# CODEC_and_Headphone_Jack.net
KiCad netlist of a schematic drawn in Altium Designer
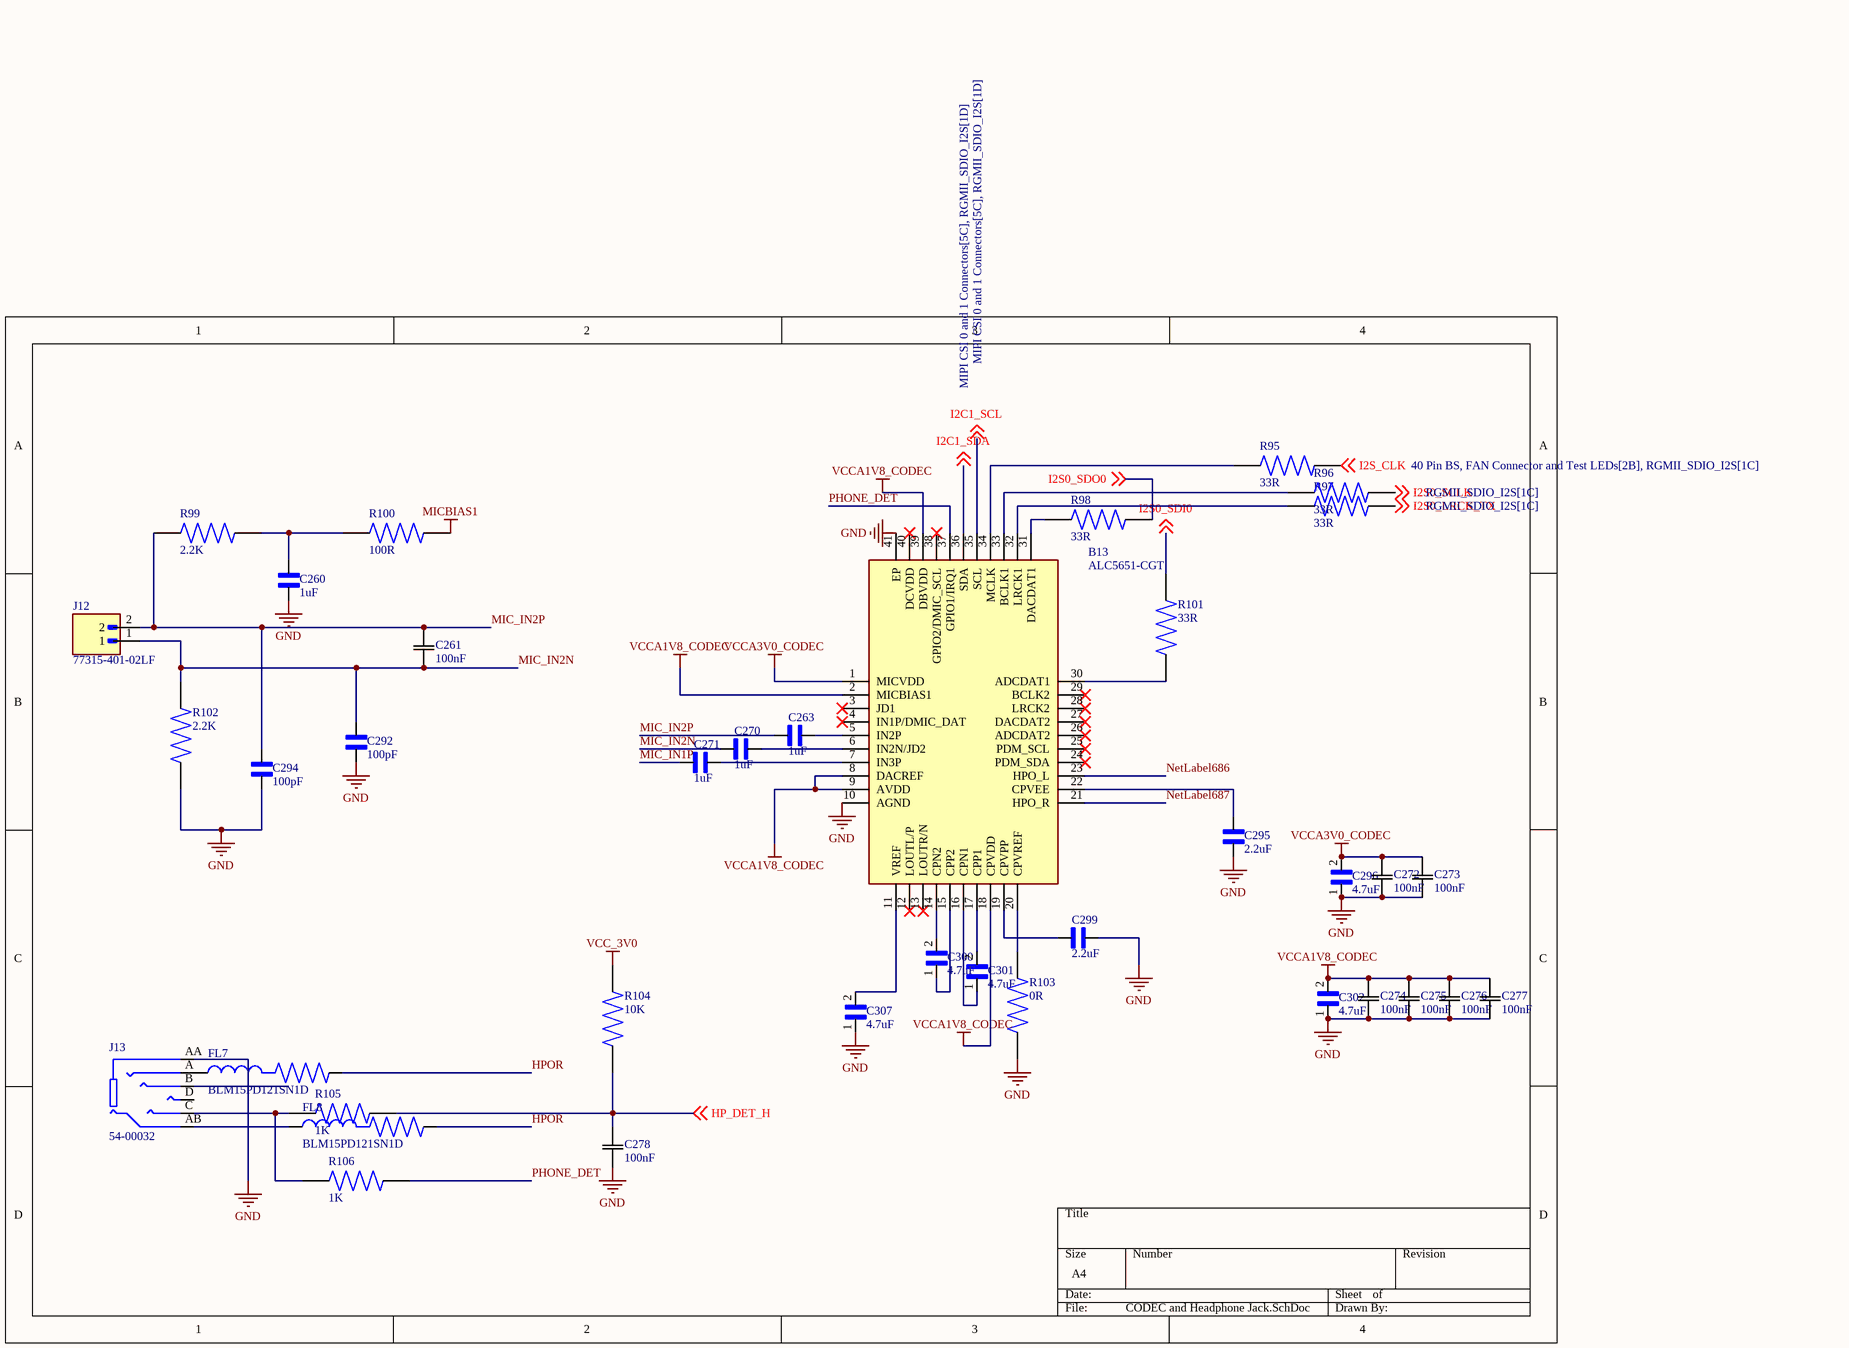
[diagram p0: CODEC and Headphone Jack.SchDoc]

(export (version "E")
  (design (tool "Eeschema 10.0.6"))
  (components
    (comp (ref "B13")
      (value "ALC5651-CGT")
      (footprint "QFN40P500X500X90-41N-D")
      (libsource (lib "ALC5651-CGT") (part "ALC5651-CGT"))
    )
    (comp (ref "C260")
      (value "1uF")
      (footprint "CAPC1005X56N")
      (description "1 ÂµF Â±10% 10V Ceramic Capacitor X5R 0402 (1005 Metric)")
      (fields (field (name "MF") "AVX") (field (name "MP") "0402ZD105KAT4A"))
      (libsource (lib "0402ZD105KAT4A") (part "0402ZD105KAT4A"))
    )
    (comp (ref "C261")
      (value "100nF")
      (footprint "CAP_1005_TDK")
      (description "Description")
      (fields
        (field (name "MANUFACTURER_PART_NUMBER") "C1005X7R1H104M050BB")
        (field (name "COPYRIGHT") "Copyright (C) 2025 Ultra Librarian. All rights reserved.")
      )
      (libsource (lib "C1005X7R1H104M050BB") (part "C1005X7R1H104M050BB"))
    )
    (comp (ref "C263")
      (value "1uF")
      (footprint "CAPC1005X56N")
      (description "1 ÂµF Â±10% 10V Ceramic Capacitor X5R 0402 (1005 Metric)")
      (fields (field (name "MF") "AVX") (field (name "MP") "0402ZD105KAT4A"))
      (libsource (lib "") (part "0402ZD105KAT4A_1"))
    )
    (comp (ref "C270")
      (value "1uF")
      (footprint "CAPC1005X56N")
      (description "1 ÂµF Â±10% 10V Ceramic Capacitor X5R 0402 (1005 Metric)")
      (fields (field (name "MF") "AVX") (field (name "MP") "0402ZD105KAT4A"))
      (libsource (lib "") (part "0402ZD105KAT4A_1"))
    )
    (comp (ref "C271")
      (value "1uF")
      (footprint "CAPC1005X56N")
      (description "1 ÂµF Â±10% 10V Ceramic Capacitor X5R 0402 (1005 Metric)")
      (fields (field (name "MF") "AVX") (field (name "MP") "0402ZD105KAT4A"))
      (libsource (lib "") (part "0402ZD105KAT4A_1"))
    )
    (comp (ref "C272")
      (value "100nF")
      (footprint "CAP_1005_TDK")
      (description "Description")
      (fields
        (field (name "MANUFACTURER_PART_NUMBER") "C1005X7R1H104M050BB")
        (field (name "COPYRIGHT") "Copyright (C) 2025 Ultra Librarian. All rights reserved.")
      )
      (libsource (lib "C1005X7R1H104M050BB") (part "C1005X7R1H104M050BB"))
    )
    (comp (ref "C273")
      (value "100nF")
      (footprint "CAP_1005_TDK")
      (description "Description")
      (fields
        (field (name "MANUFACTURER_PART_NUMBER") "C1005X7R1H104M050BB")
        (field (name "COPYRIGHT") "Copyright (C) 2025 Ultra Librarian. All rights reserved.")
      )
      (libsource (lib "C1005X7R1H104M050BB") (part "C1005X7R1H104M050BB"))
    )
    (comp (ref "C274")
      (value "100nF")
      (footprint "CAP_1005_TDK")
      (description "Description")
      (fields
        (field (name "MANUFACTURER_PART_NUMBER") "C1005X7R1H104M050BB")
        (field (name "COPYRIGHT") "Copyright (C) 2025 Ultra Librarian. All rights reserved.")
      )
      (libsource (lib "C1005X7R1H104M050BB") (part "C1005X7R1H104M050BB"))
    )
    (comp (ref "C275")
      (value "100nF")
      (footprint "CAP_1005_TDK")
      (description "Description")
      (fields
        (field (name "MANUFACTURER_PART_NUMBER") "C1005X7R1H104M050BB")
        (field (name "COPYRIGHT") "Copyright (C) 2025 Ultra Librarian. All rights reserved.")
      )
      (libsource (lib "C1005X7R1H104M050BB") (part "C1005X7R1H104M050BB"))
    )
    (comp (ref "C276")
      (value "100nF")
      (footprint "CAP_1005_TDK")
      (description "Description")
      (fields
        (field (name "MANUFACTURER_PART_NUMBER") "C1005X7R1H104M050BB")
        (field (name "COPYRIGHT") "Copyright (C) 2025 Ultra Librarian. All rights reserved.")
      )
      (libsource (lib "C1005X7R1H104M050BB") (part "C1005X7R1H104M050BB"))
    )
    (comp (ref "C277")
      (value "100nF")
      (footprint "CAP_1005_TDK")
      (description "Description")
      (fields
        (field (name "MANUFACTURER_PART_NUMBER") "C1005X7R1H104M050BB")
        (field (name "COPYRIGHT") "Copyright (C) 2025 Ultra Librarian. All rights reserved.")
      )
      (libsource (lib "C1005X7R1H104M050BB") (part "C1005X7R1H104M050BB"))
    )
    (comp (ref "C278")
      (value "100nF")
      (footprint "CAP_1005_TDK")
      (description "Description")
      (fields
        (field (name "MANUFACTURER_PART_NUMBER") "C1005X7R1H104M050BB")
        (field (name "COPYRIGHT") "Copyright (C) 2025 Ultra Librarian. All rights reserved.")
      )
      (libsource (lib "C1005X7R1H104M050BB") (part "C1005X7R1H104M050BB"))
    )
    (comp (ref "C292")
      (value "100pF")
      (footprint "CAPC2012X140N")
      (description "Capacitor, Ceramic, Cap, 22.0pF, Tol 5%, SMT, 50V, C0G ¦ KEMET C0805C220J5GACTU")
      (fields (field (name "MF") "KEMET") (field (name "MP") "C0805C220J5GACTU"))
      (libsource (lib "C0805C220J5GACTU") (part "C0805C220J5GACTU"))
    )
    (comp (ref "C294")
      (value "100pF")
      (footprint "CAPC2012X140N")
      (description "Capacitor, Ceramic, Cap, 22.0pF, Tol 5%, SMT, 50V, C0G ¦ KEMET C0805C220J5GACTU")
      (fields (field (name "MF") "KEMET") (field (name "MP") "C0805C220J5GACTU"))
      (libsource (lib "C0805C220J5GACTU") (part "C0805C220J5GACTU"))
    )
    (comp (ref "C295")
      (value "2.2uF")
      (footprint "CAPC3225X140N")
      (description "Capacitor;Ceramic;Cap;1.00uF;Tol+10%;SMT;Vol-Rtg 50V;High Cap.;X7R;TR ¦ KEMET C1210C105K5RACTU")
      (fields (field (name "MF") "KEMET") (field (name "MP") "C1210C105K5RACTU"))
      (libsource (lib "C1210C105K5RACTU") (part "C1210C105K5RACTU"))
    )
    (comp (ref "C296")
      (value "4.7uF")
      (footprint "CAPC6050X350N")
      (description "CAP CER 4.7UF 100V X7R SMD")
      (fields (field (name "MF") "TDK") (field (name "MP") "CKG57KX7R2A475M335JJ"))
      (libsource (lib "CKG57KX7R2A475M335JJ") (part "CKG57KX7R2A475M335JJ"))
    )
    (comp (ref "C299")
      (value "2.2uF")
      (footprint "CAPC3225X140N")
      (description "Capacitor;Ceramic;Cap;1.00uF;Tol+10%;SMT;Vol-Rtg 50V;High Cap.;X7R;TR ¦ KEMET C1210C105K5RACTU")
      (fields (field (name "MF") "KEMET") (field (name "MP") "C1210C105K5RACTU"))
      (libsource (lib "") (part "C1210C105K5RACTU_1"))
    )
    (comp (ref "C300")
      (value "4.7uF")
      (footprint "CAPC6050X350N")
      (description "CAP CER 4.7UF 100V X7R SMD")
      (fields (field (name "MF") "TDK") (field (name "MP") "CKG57KX7R2A475M335JJ"))
      (libsource (lib "CKG57KX7R2A475M335JJ") (part "CKG57KX7R2A475M335JJ"))
    )
    (comp (ref "C301")
      (value "4.7uF")
      (footprint "CAPC6050X350N")
      (description "CAP CER 4.7UF 100V X7R SMD")
      (fields (field (name "MF") "TDK") (field (name "MP") "CKG57KX7R2A475M335JJ"))
      (libsource (lib "CKG57KX7R2A475M335JJ") (part "CKG57KX7R2A475M335JJ"))
    )
    (comp (ref "C302")
      (value "4.7uF")
      (footprint "CAPC6050X350N")
      (description "CAP CER 4.7UF 100V X7R SMD")
      (fields (field (name "MF") "TDK") (field (name "MP") "CKG57KX7R2A475M335JJ"))
      (libsource (lib "CKG57KX7R2A475M335JJ") (part "CKG57KX7R2A475M335JJ"))
    )
    (comp (ref "C307")
      (value "4.7uF")
      (footprint "CAPC6050X350N")
      (description "CAP CER 4.7UF 100V X7R SMD")
      (fields (field (name "MF") "TDK") (field (name "MP") "CKG57KX7R2A475M335JJ"))
      (libsource (lib "CKG57KX7R2A475M335JJ") (part "CKG57KX7R2A475M335JJ"))
    )
    (comp (ref "FL7")
      (value "BLM15PD121SN1D")
      (footprint "BEADC1005X55N")
      (description "120 Ohms @ 100 MHz 1 Power Line Ferrite Bead 0402 (1005 Metric) 1.3A 90mOhm")
      (fields (field (name "MF") "Murata"))
      (libsource (lib "BLM15PD121SN1D") (part "BLM15PD121SN1D"))
    )
    (comp (ref "FL8")
      (value "BLM15PD121SN1D")
      (footprint "BEADC1005X55N")
      (description "120 Ohms @ 100 MHz 1 Power Line Ferrite Bead 0402 (1005 Metric) 1.3A 90mOhm")
      (fields (field (name "MF") "Murata"))
      (libsource (lib "BLM15PD121SN1D") (part "BLM15PD121SN1D"))
    )
    (comp (ref "J12")
      (value "77315-401-02LF")
      (footprint "AMPHENOL_77315-401-02LF")
      (libsource (lib "77315-401-02LF") (part "77315-401-02LF"))
    )
    (comp (ref "J13")
      (value "54-00032")
      (footprint "TENSILITY_54-00032")
      (description "Connector, 6C audio jack, 3.5xL18.6 mm, PCB mount, 90 degrees, Au plated")
      (fields (field (name "MF") "Tensility International"))
      (libsource (lib "54-00032") (part "54-00032"))
    )
    (comp (ref "R95")
      (value "33R")
      (footprint "RES_ERA6AHD330V")
      (fields (field (name "MP") "ERA6AHD330V"))
      (libsource (lib "ERA6AHD330V") (part "ERA6AHD330V"))
    )
    (comp (ref "R96")
      (value "33R")
      (footprint "RES_ERA6AHD330V")
      (fields (field (name "MP") "ERA6AHD330V"))
      (libsource (lib "ERA6AHD330V") (part "ERA6AHD330V"))
    )
    (comp (ref "R97")
      (value "33R")
      (footprint "RES_ERA6AHD330V")
      (fields (field (name "MP") "ERA6AHD330V"))
      (libsource (lib "ERA6AHD330V") (part "ERA6AHD330V"))
    )
    (comp (ref "R98")
      (value "33R")
      (footprint "RES_ERA6AHD330V")
      (fields (field (name "MP") "ERA6AHD330V"))
      (libsource (lib "ERA6AHD330V") (part "ERA6AHD330V"))
    )
    (comp (ref "R99")
      (value "2.2K")
      (footprint "RESC1608X50N")
      (description "RR Series 0603 0.0625 W 2.2 kOhm Â± 0.5% Â±25 ppm/Â°C SMT Metal Film Chip Resistor")
      (fields (field (name "MF") "Susumu") (field (name "MP") "RR0816P-222-D"))
      (libsource (lib "RR0816P-222-D") (part "RR0816P-222-D"))
    )
    (comp (ref "R100")
      (value "100R")
      (footprint "RES_ERJU14F1000U")
      (fields (field (name "MP") "ERJU14F1000U"))
      (libsource (lib "ERJU14F1000U") (part "ERJU14F1000U"))
    )
    (comp (ref "R101")
      (value "33R")
      (footprint "RES_ERA6AHD330V")
      (fields (field (name "MP") "ERA6AHD330V"))
      (libsource (lib "ERA6AHD330V") (part "ERA6AHD330V"))
    )
    (comp (ref "R102")
      (value "2.2K")
      (footprint "RESC1608X50N")
      (description "RR Series 0603 0.0625 W 2.2 kOhm Â± 0.5% Â±25 ppm/Â°C SMT Metal Film Chip Resistor")
      (fields (field (name "MF") "Susumu") (field (name "MP") "RR0816P-222-D"))
      (libsource (lib "RR0816P-222-D") (part "RR0816P-222-D"))
    )
    (comp (ref "R103")
      (value "0R")
      (footprint "RES_ERJH6G0R00V")
      (fields (field (name "MP") "ERJH6G0R00V"))
      (libsource (lib "ERJH6G0R00V") (part "ERJH6G0R00V"))
    )
    (comp (ref "R104")
      (value "10K")
      (footprint "RES_ERA3ARB103V")
      (fields (field (name "MP") "ERA3ARB103V"))
      (libsource (lib "ERA3ARB103V") (part "ERA3ARB103V"))
    )
    (comp (ref "R105")
      (value "1K")
      (footprint "RESC1608X55N")
      (description "1 kOhms Â±1% 0.1W, 1/10W Chip Resistor 0603 (1608 Metric) - Thick Film")
      (fields (field (name "MF") "Vishay") (field (name "MP") "CRCW06031K00FKECC"))
      (libsource (lib "CRCW06031K00FKECC") (part "CRCW06031K00FKECC"))
    )
    (comp (ref "R106")
      (value "1K")
      (footprint "RESC1608X55N")
      (description "1 kOhms Â±1% 0.1W, 1/10W Chip Resistor 0603 (1608 Metric) - Thick Film")
      (fields (field (name "MF") "Vishay") (field (name "MP") "CRCW06031K00FKECC"))
      (libsource (lib "CRCW06031K00FKECC") (part "CRCW06031K00FKECC"))
    )
  )
  (nets
    (net (code "1") (name "/HPOR") (class "Default")
      (node (ref "FL7") (pin "2") (pinfunction "2_2") (pintype "passive"))
      (node (ref "FL8") (pin "2") (pinfunction "2_2") (pintype "passive"))
    )
    (net (code "2") (name "/MIC_IN1P") (class "Default")
      (node (ref "C271") (pin "2") (pinfunction "2_2") (pintype "passive"))
    )
    (net (code "3") (name "/MIC_IN2N") (class "Default")
      (node (ref "C261") (pin "1") (pinfunction "1_1") (pintype "passive"))
      (node (ref "C270") (pin "2") (pinfunction "2_2") (pintype "passive"))
      (node (ref "C292") (pin "1") (pinfunction "1_1") (pintype "passive"))
      (node (ref "J12") (pin "1") (pinfunction "1_1") (pintype "passive"))
      (node (ref "R102") (pin "2") (pinfunction "2_2") (pintype "passive"))
    )
    (net (code "4") (name "/MIC_IN2P") (class "Default")
      (node (ref "C261") (pin "2") (pinfunction "2_2") (pintype "passive"))
      (node (ref "C263") (pin "2") (pinfunction "2_2") (pintype "passive"))
      (node (ref "C294") (pin "1") (pinfunction "1_1") (pintype "passive"))
      (node (ref "J12") (pin "2") (pinfunction "2_2") (pintype "passive"))
      (node (ref "R99") (pin "1") (pinfunction "1_1") (pintype "passive"))
    )
    (net (code "5") (name "/NetLabel686") (class "Default")
      (node (ref "B13") (pin "23") (pinfunction "HPO_L_23") (pintype "passive"))
    )
    (net (code "6") (name "/NetLabel687") (class "Default")
      (node (ref "B13") (pin "21") (pinfunction "HPO_R_21") (pintype "passive"))
    )
    (net (code "7") (name "/PHONE_DET") (class "Default")
      (node (ref "B13") (pin "37") (pinfunction "GPIO1/IRQ1_37") (pintype "passive"))
      (node (ref "R106") (pin "2") (pinfunction "2_2") (pintype "passive"))
    )
    (net (code "8") (name "GND") (class "Default")
      (node (ref "B13") (pin "10") (pinfunction "AGND_10") (pintype "passive"))
      (node (ref "B13") (pin "41") (pinfunction "EP_41") (pintype "passive"))
      (node (ref "C260") (pin "1") (pinfunction "1_1") (pintype "passive"))
      (node (ref "C272") (pin "1") (pinfunction "1_1") (pintype "passive"))
      (node (ref "C273") (pin "1") (pinfunction "1_1") (pintype "passive"))
      (node (ref "C274") (pin "1") (pinfunction "1_1") (pintype "passive"))
      (node (ref "C275") (pin "1") (pinfunction "1_1") (pintype "passive"))
      (node (ref "C276") (pin "1") (pinfunction "1_1") (pintype "passive"))
      (node (ref "C277") (pin "1") (pinfunction "1_1") (pintype "passive"))
      (node (ref "C278") (pin "1") (pinfunction "1_1") (pintype "passive"))
      (node (ref "C292") (pin "2") (pinfunction "2_2") (pintype "passive"))
      (node (ref "C294") (pin "2") (pinfunction "2_2") (pintype "passive"))
      (node (ref "C295") (pin "1") (pinfunction "1_1") (pintype "passive"))
      (node (ref "C296") (pin "1") (pinfunction "1_1") (pintype "passive"))
      (node (ref "C299") (pin "1") (pinfunction "1_1") (pintype "passive"))
      (node (ref "C302") (pin "1") (pinfunction "1_1") (pintype "passive"))
      (node (ref "C307") (pin "1") (pinfunction "1_1") (pintype "passive"))
      (node (ref "J13") (pin "AA") (pinfunction "AA_AA") (pintype "passive"))
      (node (ref "R102") (pin "1") (pinfunction "1_1") (pintype "passive"))
      (node (ref "R103") (pin "1") (pinfunction "1_1") (pintype "passive"))
    )
    (net (code "9") (name "HP_DET_H") (class "Default")
      (node (ref "C278") (pin "2") (pinfunction "2_2") (pintype "passive"))
      (node (ref "R104") (pin "1") (pinfunction "1_1") (pintype "passive"))
      (node (ref "R105") (pin "2") (pinfunction "2_2") (pintype "passive"))
    )
    (net (code "10") (name "I2C1_SCL") (class "Default")
      (node (ref "B13") (pin "35") (pinfunction "SCL_35") (pintype "passive"))
    )
    (net (code "11") (name "I2C1_SDA") (class "Default")
      (node (ref "B13") (pin "36") (pinfunction "SDA_36") (pintype "passive"))
    )
    (net (code "12") (name "I2S0_LRCK_TX") (class "Default")
      (node (ref "R97") (pin "1") (pinfunction "1_1") (pintype "passive"))
    )
    (net (code "13") (name "I2S0_SCLK") (class "Default")
      (node (ref "R96") (pin "1") (pinfunction "1_1") (pintype "passive"))
    )
    (net (code "14") (name "I2S0_SDI0") (class "Default")
      (node (ref "R101") (pin "2") (pinfunction "2_2") (pintype "passive"))
    )
    (net (code "15") (name "I2S0_SDO0") (class "Default")
      (node (ref "R98") (pin "2") (pinfunction "2_2") (pintype "passive"))
    )
    (net (code "16") (name "I2S_CLK") (class "Default")
      (node (ref "R95") (pin "1") (pinfunction "1_1") (pintype "passive"))
    )
    (net (code "17") (name "MICBIAS1") (class "Default")
      (node (ref "R100") (pin "2") (pinfunction "2_2") (pintype "passive"))
    )
    (net (code "18") (name "Net-(B13-ADCDAT1)") (class "Default")
      (node (ref "B13") (pin "30") (pinfunction "ADCDAT1_30") (pintype "passive"))
      (node (ref "R101") (pin "1") (pinfunction "1_1") (pintype "passive"))
    )
    (net (code "19") (name "Net-(B13-BCLK1)") (class "Default")
      (node (ref "B13") (pin "33") (pinfunction "BCLK1_33") (pintype "passive"))
      (node (ref "R96") (pin "2") (pinfunction "2_2") (pintype "passive"))
    )
    (net (code "20") (name "Net-(B13-CPN1)") (class "Default")
      (node (ref "B13") (pin "16") (pinfunction "CPN1_16") (pintype "passive"))
      (node (ref "C301") (pin "1") (pinfunction "1_1") (pintype "passive"))
    )
    (net (code "21") (name "Net-(B13-CPN2)") (class "Default")
      (node (ref "B13") (pin "14") (pinfunction "CPN2_14") (pintype "passive"))
      (node (ref "C300") (pin "2") (pinfunction "2_2") (pintype "passive"))
    )
    (net (code "22") (name "Net-(B13-CPP1)") (class "Default")
      (node (ref "B13") (pin "17") (pinfunction "CPP1_17") (pintype "passive"))
      (node (ref "C301") (pin "2") (pinfunction "2_2") (pintype "passive"))
    )
    (net (code "23") (name "Net-(B13-CPP2)") (class "Default")
      (node (ref "B13") (pin "15") (pinfunction "CPP2_15") (pintype "passive"))
      (node (ref "C300") (pin "1") (pinfunction "1_1") (pintype "passive"))
    )
    (net (code "24") (name "Net-(B13-CPVEE)") (class "Default")
      (node (ref "B13") (pin "22") (pinfunction "CPVEE_22") (pintype "passive"))
      (node (ref "C295") (pin "2") (pinfunction "2_2") (pintype "passive"))
    )
    (net (code "25") (name "Net-(B13-CPVPP)") (class "Default")
      (node (ref "B13") (pin "19") (pinfunction "CPVPP_19") (pintype "passive"))
      (node (ref "C299") (pin "2") (pinfunction "2_2") (pintype "passive"))
    )
    (net (code "26") (name "Net-(B13-CPVREF)") (class "Default")
      (node (ref "B13") (pin "20") (pinfunction "CPVREF_20") (pintype "passive"))
      (node (ref "R103") (pin "2") (pinfunction "2_2") (pintype "passive"))
    )
    (net (code "27") (name "Net-(B13-DACDAT1)") (class "Default")
      (node (ref "B13") (pin "31") (pinfunction "DACDAT1_31") (pintype "passive"))
      (node (ref "R98") (pin "1") (pinfunction "1_1") (pintype "passive"))
    )
    (net (code "28") (name "Net-(B13-IN2N{slash}JD2)") (class "Default")
      (node (ref "B13") (pin "6") (pinfunction "IN2N/JD2_6") (pintype "passive"))
      (node (ref "C270") (pin "1") (pinfunction "1_1") (pintype "passive"))
    )
    (net (code "29") (name "Net-(B13-IN2P)") (class "Default")
      (node (ref "B13") (pin "5") (pinfunction "IN2P_5") (pintype "passive"))
      (node (ref "C263") (pin "1") (pinfunction "1_1") (pintype "passive"))
    )
    (net (code "30") (name "Net-(B13-IN3P)") (class "Default")
      (node (ref "B13") (pin "7") (pinfunction "IN3P_7") (pintype "passive"))
      (node (ref "C271") (pin "1") (pinfunction "1_1") (pintype "passive"))
    )
    (net (code "31") (name "Net-(B13-LRCK1)") (class "Default")
      (node (ref "B13") (pin "32") (pinfunction "LRCK1_32") (pintype "passive"))
      (node (ref "R97") (pin "2") (pinfunction "2_2") (pintype "passive"))
    )
    (net (code "32") (name "Net-(B13-MCLK)") (class "Default")
      (node (ref "B13") (pin "34") (pinfunction "MCLK_34") (pintype "passive"))
      (node (ref "R95") (pin "2") (pinfunction "2_2") (pintype "passive"))
    )
    (net (code "33") (name "Net-(B13-VREF)") (class "Default")
      (node (ref "B13") (pin "11") (pinfunction "VREF_11") (pintype "passive"))
      (node (ref "C307") (pin "2") (pinfunction "2_2") (pintype "passive"))
    )
    (net (code "34") (name "Net-(C260-Pad2)") (class "Default")
      (node (ref "C260") (pin "2") (pinfunction "2_2") (pintype "passive"))
      (node (ref "R100") (pin "1") (pinfunction "1_1") (pintype "passive"))
      (node (ref "R99") (pin "2") (pinfunction "2_2") (pintype "passive"))
    )
    (net (code "35") (name "Net-(FL7-Pad1)") (class "Default")
      (node (ref "FL7") (pin "1") (pinfunction "1_1") (pintype "passive"))
      (node (ref "J13") (pin "A") (pinfunction "A_A") (pintype "passive"))
    )
    (net (code "36") (name "Net-(FL8-Pad1)") (class "Default")
      (node (ref "FL8") (pin "1") (pinfunction "1_1") (pintype "passive"))
      (node (ref "J13") (pin "AB") (pinfunction "AB_AB") (pintype "passive"))
    )
    (net (code "37") (name "Net-(J13-PadC)") (class "Default")
      (node (ref "J13") (pin "C") (pinfunction "C_C") (pintype "passive"))
      (node (ref "R105") (pin "1") (pinfunction "1_1") (pintype "passive"))
      (node (ref "R106") (pin "1") (pinfunction "1_1") (pintype "passive"))
    )
    (net (code "38") (name "VCCA1V8_CODEC") (class "Default")
      (node (ref "B13") (pin "18") (pinfunction "CPVDD_18") (pintype "passive"))
      (node (ref "B13") (pin "2") (pinfunction "MICBIAS1_2") (pintype "passive"))
      (node (ref "B13") (pin "39") (pinfunction "DBVDD_39") (pintype "passive"))
      (node (ref "B13") (pin "8") (pinfunction "DACREF_8") (pintype "passive"))
      (node (ref "B13") (pin "9") (pinfunction "AVDD_9") (pintype "passive"))
      (node (ref "C274") (pin "2") (pinfunction "2_2") (pintype "passive"))
      (node (ref "C275") (pin "2") (pinfunction "2_2") (pintype "passive"))
      (node (ref "C276") (pin "2") (pinfunction "2_2") (pintype "passive"))
      (node (ref "C277") (pin "2") (pinfunction "2_2") (pintype "passive"))
      (node (ref "C302") (pin "2") (pinfunction "2_2") (pintype "passive"))
    )
    (net (code "39") (name "VCCA3V0_CODEC") (class "Default")
      (node (ref "B13") (pin "1") (pinfunction "MICVDD_1") (pintype "passive"))
      (node (ref "C272") (pin "2") (pinfunction "2_2") (pintype "passive"))
      (node (ref "C273") (pin "2") (pinfunction "2_2") (pintype "passive"))
      (node (ref "C296") (pin "2") (pinfunction "2_2") (pintype "passive"))
    )
    (net (code "40") (name "VCC_3V0") (class "Default")
      (node (ref "R104") (pin "2") (pinfunction "2_2") (pintype "passive"))
    )
    (net (code "41") (name "unconnected-(B13-ADCDAT2-Pad26)") (class "Default")
      (node (ref "B13") (pin "26") (pinfunction "ADCDAT2_26") (pintype "passive+no_connect"))
    )
    (net (code "42") (name "unconnected-(B13-BCLK2-Pad29)") (class "Default")
      (node (ref "B13") (pin "29") (pinfunction "BCLK2_29") (pintype "passive+no_connect"))
    )
    (net (code "43") (name "unconnected-(B13-DACDAT2-Pad27)") (class "Default")
      (node (ref "B13") (pin "27") (pinfunction "DACDAT2_27") (pintype "passive+no_connect"))
    )
    (net (code "44") (name "unconnected-(B13-DCVDD-Pad40)") (class "Default")
      (node (ref "B13") (pin "40") (pinfunction "DCVDD_40") (pintype "passive+no_connect"))
    )
    (net (code "45") (name "unconnected-(B13-GPIO2{slash}DMIC_SCL-Pad38)") (class "Default")
      (node (ref "B13") (pin "38") (pinfunction "GPIO2/DMIC_SCL_38") (pintype "passive+no_connect"))
    )
    (net (code "46") (name "unconnected-(B13-IN1P{slash}DMIC_DAT-Pad4)") (class "Default")
      (node (ref "B13") (pin "4") (pinfunction "IN1P/DMIC_DAT_4") (pintype "passive+no_connect"))
    )
    (net (code "47") (name "unconnected-(B13-JD1-Pad3)") (class "Default")
      (node (ref "B13") (pin "3") (pinfunction "JD1_3") (pintype "passive+no_connect"))
    )
    (net (code "48") (name "unconnected-(B13-LOUTL{slash}P-Pad12)") (class "Default")
      (node (ref "B13") (pin "12") (pinfunction "LOUTL/P_12") (pintype "passive+no_connect"))
    )
    (net (code "49") (name "unconnected-(B13-LOUTR{slash}N-Pad13)") (class "Default")
      (node (ref "B13") (pin "13") (pinfunction "LOUTR/N_13") (pintype "passive+no_connect"))
    )
    (net (code "50") (name "unconnected-(B13-LRCK2-Pad28)") (class "Default")
      (node (ref "B13") (pin "28") (pinfunction "LRCK2_28") (pintype "passive+no_connect"))
    )
    (net (code "51") (name "unconnected-(B13-PDM_SCL-Pad25)") (class "Default")
      (node (ref "B13") (pin "25") (pinfunction "PDM_SCL_25") (pintype "passive+no_connect"))
    )
    (net (code "52") (name "unconnected-(B13-PDM_SDA-Pad24)") (class "Default")
      (node (ref "B13") (pin "24") (pinfunction "PDM_SDA_24") (pintype "passive+no_connect"))
    )
    (net (code "53") (name "unconnected-(J13-PadB)") (class "Default")
      (node (ref "J13") (pin "B") (pinfunction "B_B") (pintype "passive"))
    )
    (net (code "54") (name "unconnected-(J13-PadD)") (class "Default")
      (node (ref "J13") (pin "D") (pinfunction "D_D") (pintype "passive"))
    )
  )
)
